# IO_Combo_LED_Monitor.net
KiCad netlist of a schematic drawn in Altium Designer
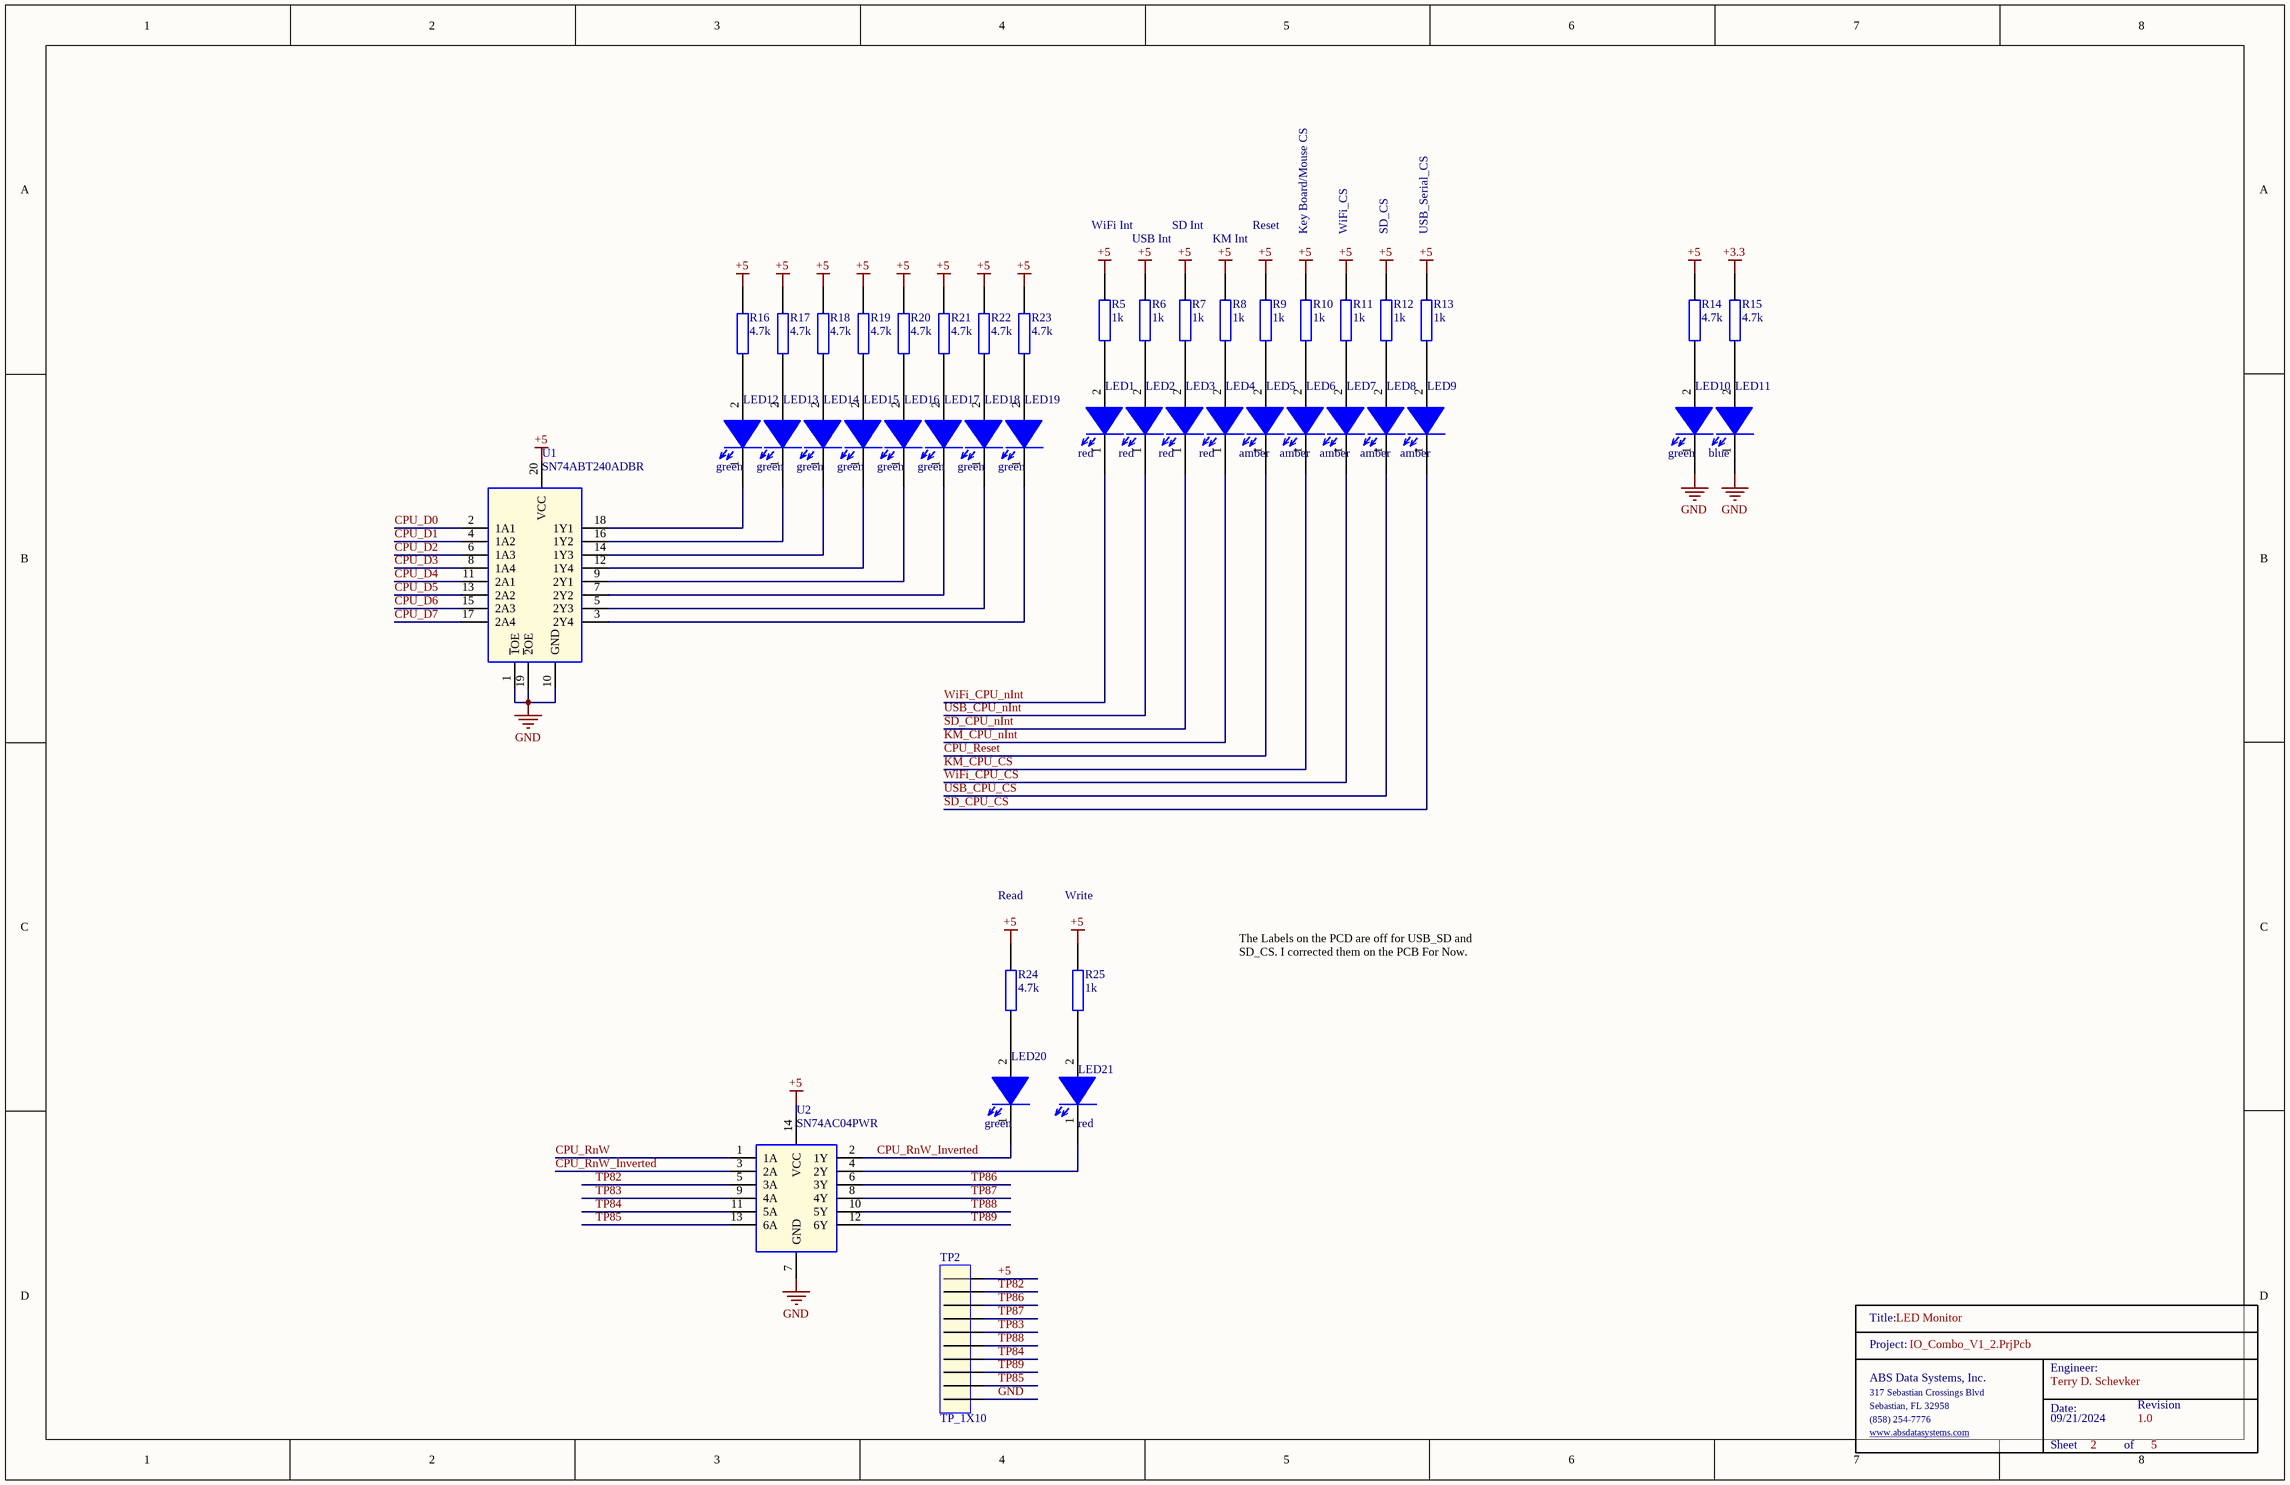
[diagram p0: IO_Combo_LED_Monitor.SchDoc]

(export (version "E")
  (design (tool "Eeschema 10.0.6"))
  (components
    (comp (ref "LED1")
      (value "red")
      (footprint "0603_Diode")
      (description "Wurth Elektronik 0603 red")
      (fields
        (field (name "MANUFACTURER") "Wurth Electronics")
        (field (name "MANUFACTURER PART NUMBER") "150060GS75000")
      )
      (libsource (lib "Misc") (part "150060RS75000"))
    )
    (comp (ref "LED2")
      (value "red")
      (footprint "0603_Diode")
      (description "Wurth Elektronik 0603 red")
      (fields
        (field (name "MANUFACTURER") "Wurth Electronics")
        (field (name "MANUFACTURER PART NUMBER") "150060GS75000")
      )
      (libsource (lib "Misc") (part "150060RS75000"))
    )
    (comp (ref "LED3")
      (value "red")
      (footprint "0603_Diode")
      (description "Wurth Elektronik 0603 red")
      (fields
        (field (name "MANUFACTURER") "Wurth Electronics")
        (field (name "MANUFACTURER PART NUMBER") "150060GS75000")
      )
      (libsource (lib "Misc") (part "150060RS75000"))
    )
    (comp (ref "LED4")
      (value "red")
      (footprint "0603_Diode")
      (description "Wurth Elektronik 0603 red")
      (fields
        (field (name "MANUFACTURER") "Wurth Electronics")
        (field (name "MANUFACTURER PART NUMBER") "150060GS75000")
      )
      (libsource (lib "Misc") (part "150060RS75000"))
    )
    (comp (ref "LED5")
      (value "amber")
      (footprint "0603_Diode")
      (description "Wurth Elektronik 0603 amber")
      (fields
        (field (name "MANUFACTURER") "Wurth Electronics")
        (field (name "MANUFACTURER PART NUMBER") "150060GS75000")
      )
      (libsource (lib "Misc") (part "150060AS75000"))
    )
    (comp (ref "LED6")
      (value "amber")
      (footprint "0603_Diode")
      (description "Wurth Elektronik 0603 amber")
      (fields
        (field (name "MANUFACTURER") "Wurth Electronics")
        (field (name "MANUFACTURER PART NUMBER") "150060GS75000")
      )
      (libsource (lib "Misc") (part "150060AS75000"))
    )
    (comp (ref "LED7")
      (value "amber")
      (footprint "0603_Diode")
      (description "Wurth Elektronik 0603 amber")
      (fields
        (field (name "MANUFACTURER") "Wurth Electronics")
        (field (name "MANUFACTURER PART NUMBER") "150060GS75000")
      )
      (libsource (lib "Misc") (part "150060AS75000"))
    )
    (comp (ref "LED8")
      (value "amber")
      (footprint "0603_Diode")
      (description "Wurth Elektronik 0603 amber")
      (fields
        (field (name "MANUFACTURER") "Wurth Electronics")
        (field (name "MANUFACTURER PART NUMBER") "150060GS75000")
      )
      (libsource (lib "Misc") (part "150060AS75000"))
    )
    (comp (ref "LED9")
      (value "amber")
      (footprint "0603_Diode")
      (description "Wurth Elektronik 0603 amber")
      (fields
        (field (name "MANUFACTURER") "Wurth Electronics")
        (field (name "MANUFACTURER PART NUMBER") "150060GS75000")
      )
      (libsource (lib "Misc") (part "150060AS75000"))
    )
    (comp (ref "LED10")
      (value "green")
      (footprint "0603_Diode")
      (description "Wurth Elektronik 0603 green")
      (fields
        (field (name "MANUFACTURER") "Wurth Electronics")
        (field (name "MANUFACTURER PART NUMBER") "150060GS75000")
      )
      (libsource (lib "Misc") (part "150060GS75000"))
    )
    (comp (ref "LED11")
      (value "blue")
      (footprint "0603_Diode")
      (description "Wurth Elektronik 0603 blue")
      (fields
        (field (name "MANUFACTURER") "Wurth Electronics")
        (field (name "MANUFACTURER PART NUMBER") "150060GS75000")
      )
      (libsource (lib "Misc") (part "150060BS75000"))
    )
    (comp (ref "LED12")
      (value "green")
      (footprint "0603_Diode")
      (description "Wurth Elektronik 0603 green")
      (fields
        (field (name "MANUFACTURER") "Wurth Electronics")
        (field (name "MANUFACTURER PART NUMBER") "150060GS75000")
      )
      (libsource (lib "Misc") (part "150060GS75000"))
    )
    (comp (ref "LED13")
      (value "green")
      (footprint "0603_Diode")
      (description "Wurth Elektronik 0603 green")
      (fields
        (field (name "MANUFACTURER") "Wurth Electronics")
        (field (name "MANUFACTURER PART NUMBER") "150060GS75000")
      )
      (libsource (lib "Misc") (part "150060GS75000"))
    )
    (comp (ref "LED14")
      (value "green")
      (footprint "0603_Diode")
      (description "Wurth Elektronik 0603 green")
      (fields
        (field (name "MANUFACTURER") "Wurth Electronics")
        (field (name "MANUFACTURER PART NUMBER") "150060GS75000")
      )
      (libsource (lib "Misc") (part "150060GS75000"))
    )
    (comp (ref "LED15")
      (value "green")
      (footprint "0603_Diode")
      (description "Wurth Elektronik 0603 green")
      (fields
        (field (name "MANUFACTURER") "Wurth Electronics")
        (field (name "MANUFACTURER PART NUMBER") "150060GS75000")
      )
      (libsource (lib "Misc") (part "150060GS75000"))
    )
    (comp (ref "LED16")
      (value "green")
      (footprint "0603_Diode")
      (description "Wurth Elektronik 0603 green")
      (fields
        (field (name "MANUFACTURER") "Wurth Electronics")
        (field (name "MANUFACTURER PART NUMBER") "150060GS75000")
      )
      (libsource (lib "Misc") (part "150060GS75000"))
    )
    (comp (ref "LED17")
      (value "green")
      (footprint "0603_Diode")
      (description "Wurth Elektronik 0603 green")
      (fields
        (field (name "MANUFACTURER") "Wurth Electronics")
        (field (name "MANUFACTURER PART NUMBER") "150060GS75000")
      )
      (libsource (lib "Misc") (part "150060GS75000"))
    )
    (comp (ref "LED18")
      (value "green")
      (footprint "0603_Diode")
      (description "Wurth Elektronik 0603 green")
      (fields
        (field (name "MANUFACTURER") "Wurth Electronics")
        (field (name "MANUFACTURER PART NUMBER") "150060GS75000")
      )
      (libsource (lib "Misc") (part "150060GS75000"))
    )
    (comp (ref "LED19")
      (value "green")
      (footprint "0603_Diode")
      (description "Wurth Elektronik 0603 green")
      (fields
        (field (name "MANUFACTURER") "Wurth Electronics")
        (field (name "MANUFACTURER PART NUMBER") "150060GS75000")
      )
      (libsource (lib "Misc") (part "150060GS75000"))
    )
    (comp (ref "LED20")
      (value "green")
      (footprint "0603_Diode")
      (description "Wurth Elektronik 0603 green")
      (fields
        (field (name "MANUFACTURER") "Wurth Electronics")
        (field (name "MANUFACTURER PART NUMBER") "150060GS75000")
      )
      (libsource (lib "Misc") (part "150060GS75000"))
    )
    (comp (ref "LED21")
      (value "red")
      (footprint "0603_Diode")
      (description "Wurth Elektronik 0603 red")
      (fields
        (field (name "MANUFACTURER") "Wurth Electronics")
        (field (name "MANUFACTURER PART NUMBER") "150060GS75000")
      )
      (libsource (lib "Misc") (part "150060RS75000"))
    )
    (comp (ref "R5")
      (value "1k")
      (footprint "0603")
      (description "YAGEO 0603 1k ohm")
      (fields
        (field (name "MOUSER PART NUMBER") "603-RC0603JR-070RL")
        (field (name "MANUFACTURER_PART_NUMBER") "RC0603JR-070RL")
      )
      (libsource (lib "Resistors") (part "AC0603FR-7W1KL_1"))
    )
    (comp (ref "R6")
      (value "1k")
      (footprint "0603")
      (description "YAGEO 0603 1k ohm")
      (fields
        (field (name "MOUSER PART NUMBER") "603-RC0603JR-070RL")
        (field (name "MANUFACTURER_PART_NUMBER") "RC0603JR-070RL")
      )
      (libsource (lib "Resistors") (part "AC0603FR-7W1KL_1"))
    )
    (comp (ref "R7")
      (value "1k")
      (footprint "0603")
      (description "YAGEO 0603 1k ohm")
      (fields
        (field (name "MOUSER PART NUMBER") "603-RC0603JR-070RL")
        (field (name "MANUFACTURER_PART_NUMBER") "RC0603JR-070RL")
      )
      (libsource (lib "Resistors") (part "AC0603FR-7W1KL_1"))
    )
    (comp (ref "R8")
      (value "1k")
      (footprint "0603")
      (description "YAGEO 0603 1k ohm")
      (fields
        (field (name "MOUSER PART NUMBER") "603-RC0603JR-070RL")
        (field (name "MANUFACTURER_PART_NUMBER") "RC0603JR-070RL")
      )
      (libsource (lib "Resistors") (part "AC0603FR-7W1KL_1"))
    )
    (comp (ref "R9")
      (value "1k")
      (footprint "0603")
      (description "YAGEO 0603 1k ohm")
      (fields
        (field (name "MOUSER PART NUMBER") "603-RC0603JR-070RL")
        (field (name "MANUFACTURER_PART_NUMBER") "RC0603JR-070RL")
      )
      (libsource (lib "Resistors") (part "AC0603FR-7W1KL_1"))
    )
    (comp (ref "R10")
      (value "1k")
      (footprint "0603")
      (description "YAGEO 0603 1k ohm")
      (fields
        (field (name "MOUSER PART NUMBER") "603-RC0603JR-070RL")
        (field (name "MANUFACTURER_PART_NUMBER") "RC0603JR-070RL")
      )
      (libsource (lib "Resistors") (part "AC0603FR-7W1KL_1"))
    )
    (comp (ref "R11")
      (value "1k")
      (footprint "0603")
      (description "YAGEO 0603 1k ohm")
      (fields
        (field (name "MOUSER PART NUMBER") "603-RC0603JR-070RL")
        (field (name "MANUFACTURER_PART_NUMBER") "RC0603JR-070RL")
      )
      (libsource (lib "Resistors") (part "AC0603FR-7W1KL_1"))
    )
    (comp (ref "R12")
      (value "1k")
      (footprint "0603")
      (description "YAGEO 0603 1k ohm")
      (fields
        (field (name "MOUSER PART NUMBER") "603-RC0603JR-070RL")
        (field (name "MANUFACTURER_PART_NUMBER") "RC0603JR-070RL")
      )
      (libsource (lib "Resistors") (part "AC0603FR-7W1KL_1"))
    )
    (comp (ref "R13")
      (value "1k")
      (footprint "0603")
      (description "YAGEO 0603 1k ohm")
      (fields
        (field (name "MOUSER PART NUMBER") "603-RC0603JR-070RL")
        (field (name "MANUFACTURER_PART_NUMBER") "RC0603JR-070RL")
      )
      (libsource (lib "Resistors") (part "AC0603FR-7W1KL_1"))
    )
    (comp (ref "R14")
      (value "4.7k")
      (footprint "0603")
      (description "YAGEO 0603 4.7k")
      (fields
        (field (name "MOUSER PART NUMBER") "603-RC0603JR-070RL")
        (field (name "MANUFACTURER_PART_NUMBER") "RC0603JR-070RL")
      )
      (libsource (lib "Resistors") (part "RC0603FR-104K7L"))
    )
    (comp (ref "R15")
      (value "4.7k")
      (footprint "0603")
      (description "YAGEO 0603 4.7k")
      (fields
        (field (name "MOUSER PART NUMBER") "603-RC0603JR-070RL")
        (field (name "MANUFACTURER_PART_NUMBER") "RC0603JR-070RL")
      )
      (libsource (lib "Resistors") (part "RC0603FR-104K7L"))
    )
    (comp (ref "R16")
      (value "4.7k")
      (footprint "0603")
      (description "YAGEO 0603 4.7k")
      (fields
        (field (name "MOUSER PART NUMBER") "603-RC0603JR-070RL")
        (field (name "MANUFACTURER_PART_NUMBER") "RC0603JR-070RL")
      )
      (libsource (lib "Resistors") (part "RC0603FR-104K7L"))
    )
    (comp (ref "R17")
      (value "4.7k")
      (footprint "0603")
      (description "YAGEO 0603 4.7k")
      (fields
        (field (name "MOUSER PART NUMBER") "603-RC0603JR-070RL")
        (field (name "MANUFACTURER_PART_NUMBER") "RC0603JR-070RL")
      )
      (libsource (lib "Resistors") (part "RC0603FR-104K7L"))
    )
    (comp (ref "R18")
      (value "4.7k")
      (footprint "0603")
      (description "YAGEO 0603 4.7k")
      (fields
        (field (name "MOUSER PART NUMBER") "603-RC0603JR-070RL")
        (field (name "MANUFACTURER_PART_NUMBER") "RC0603JR-070RL")
      )
      (libsource (lib "Resistors") (part "RC0603FR-104K7L"))
    )
    (comp (ref "R19")
      (value "4.7k")
      (footprint "0603")
      (description "YAGEO 0603 4.7k")
      (fields
        (field (name "MOUSER PART NUMBER") "603-RC0603JR-070RL")
        (field (name "MANUFACTURER_PART_NUMBER") "RC0603JR-070RL")
      )
      (libsource (lib "Resistors") (part "RC0603FR-104K7L"))
    )
    (comp (ref "R20")
      (value "4.7k")
      (footprint "0603")
      (description "YAGEO 0603 4.7k")
      (fields
        (field (name "MOUSER PART NUMBER") "603-RC0603JR-070RL")
        (field (name "MANUFACTURER_PART_NUMBER") "RC0603JR-070RL")
      )
      (libsource (lib "Resistors") (part "RC0603FR-104K7L"))
    )
    (comp (ref "R21")
      (value "4.7k")
      (footprint "0603")
      (description "YAGEO 0603 4.7k")
      (fields
        (field (name "MOUSER PART NUMBER") "603-RC0603JR-070RL")
        (field (name "MANUFACTURER_PART_NUMBER") "RC0603JR-070RL")
      )
      (libsource (lib "Resistors") (part "RC0603FR-104K7L"))
    )
    (comp (ref "R22")
      (value "4.7k")
      (footprint "0603")
      (description "YAGEO 0603 4.7k")
      (fields
        (field (name "MOUSER PART NUMBER") "603-RC0603JR-070RL")
        (field (name "MANUFACTURER_PART_NUMBER") "RC0603JR-070RL")
      )
      (libsource (lib "Resistors") (part "RC0603FR-104K7L"))
    )
    (comp (ref "R23")
      (value "4.7k")
      (footprint "0603")
      (description "YAGEO 0603 4.7k")
      (fields
        (field (name "MOUSER PART NUMBER") "603-RC0603JR-070RL")
        (field (name "MANUFACTURER_PART_NUMBER") "RC0603JR-070RL")
      )
      (libsource (lib "Resistors") (part "RC0603FR-104K7L"))
    )
    (comp (ref "R24")
      (value "4.7k")
      (footprint "0603")
      (description "YAGEO 0603 4.7k")
      (fields
        (field (name "MOUSER PART NUMBER") "603-RC0603JR-070RL")
        (field (name "MANUFACTURER_PART_NUMBER") "RC0603JR-070RL")
      )
      (libsource (lib "Resistors") (part "RC0603FR-104K7L"))
    )
    (comp (ref "R25")
      (value "1k")
      (footprint "0603")
      (description "YAGEO 0603 1k ohm")
      (fields
        (field (name "MOUSER PART NUMBER") "603-RC0603JR-070RL")
        (field (name "MANUFACTURER_PART_NUMBER") "RC0603JR-070RL")
      )
      (libsource (lib "Resistors") (part "AC0603FR-7W1KL_1"))
    )
    (comp (ref "TP2")
      (value "TP_1X10")
      (footprint "TP_1X10")
      (fields
        (field (name "MANUFACTURER") "Samtec")
        (field (name "MANUFACTURER PART NUMBER") "TST-105-01-G-D")
      )
      (libsource (lib "Misc") (part "TP_1X10"))
    )
    (comp (ref "U1")
      (value "SN74ABT240ADBR")
      (footprint "SOP65P780X200-20N")
      (description "Octal Buffers/Drivers With 3-State Outputs")
      (fields (field (name "MOUSER PART NUMBER") "595-SN74ABT240ADBR"))
      (libsource (lib "Logic") (part "SN74ABT240ADBR"))
    )
    (comp (ref "U2")
      (value "SN74AC04PWR")
      (footprint "SOP65P640X120-14N")
      (description "Hex Inverters")
      (fields (field (name "MOUSER PART NUMBER") "595-SN74AC04PWR"))
      (libsource (lib "Logic") (part "SN74AC04PWR"))
    )
  )
  (nets
    (net (code "1") (name "+3.3") (class "Default")
      (node (ref "R15") (pin "2") (pinfunction "2_2") (pintype "passive"))
    )
    (net (code "2") (name "+5") (class "Default")
      (node (ref "R10") (pin "2") (pinfunction "2_2") (pintype "passive"))
      (node (ref "R11") (pin "2") (pinfunction "2_2") (pintype "passive"))
      (node (ref "R12") (pin "2") (pinfunction "2_2") (pintype "passive"))
      (node (ref "R13") (pin "2") (pinfunction "2_2") (pintype "passive"))
      (node (ref "R14") (pin "2") (pinfunction "2_2") (pintype "passive"))
      (node (ref "R16") (pin "2") (pinfunction "2_2") (pintype "passive"))
      (node (ref "R17") (pin "2") (pinfunction "2_2") (pintype "passive"))
      (node (ref "R18") (pin "2") (pinfunction "2_2") (pintype "passive"))
      (node (ref "R19") (pin "2") (pinfunction "2_2") (pintype "passive"))
      (node (ref "R20") (pin "2") (pinfunction "2_2") (pintype "passive"))
      (node (ref "R21") (pin "2") (pinfunction "2_2") (pintype "passive"))
      (node (ref "R22") (pin "2") (pinfunction "2_2") (pintype "passive"))
      (node (ref "R23") (pin "2") (pinfunction "2_2") (pintype "passive"))
      (node (ref "R24") (pin "2") (pinfunction "2_2") (pintype "passive"))
      (node (ref "R25") (pin "2") (pinfunction "2_2") (pintype "passive"))
      (node (ref "R5") (pin "2") (pinfunction "2_2") (pintype "passive"))
      (node (ref "R6") (pin "2") (pinfunction "2_2") (pintype "passive"))
      (node (ref "R7") (pin "2") (pinfunction "2_2") (pintype "passive"))
      (node (ref "R8") (pin "2") (pinfunction "2_2") (pintype "passive"))
      (node (ref "R9") (pin "2") (pinfunction "2_2") (pintype "passive"))
      (node (ref "TP2") (pin "1") (pinfunction "1_1") (pintype "passive"))
      (node (ref "U1") (pin "20") (pinfunction "VCC_20") (pintype "passive"))
      (node (ref "U2") (pin "14") (pinfunction "VCC_14") (pintype "passive"))
    )
    (net (code "3") (name "/CPU_D0") (class "Default")
      (node (ref "U1") (pin "2") (pinfunction "1A1_2") (pintype "passive"))
    )
    (net (code "4") (name "/CPU_D1") (class "Default")
      (node (ref "U1") (pin "4") (pinfunction "1A2_4") (pintype "passive"))
    )
    (net (code "5") (name "/CPU_D2") (class "Default")
      (node (ref "U1") (pin "6") (pinfunction "1A3_6") (pintype "passive"))
    )
    (net (code "6") (name "/CPU_D3") (class "Default")
      (node (ref "U1") (pin "8") (pinfunction "1A4_8") (pintype "passive"))
    )
    (net (code "7") (name "/CPU_D4") (class "Default")
      (node (ref "U1") (pin "11") (pinfunction "2A1_11") (pintype "passive"))
    )
    (net (code "8") (name "/CPU_D5") (class "Default")
      (node (ref "U1") (pin "13") (pinfunction "2A2_13") (pintype "passive"))
    )
    (net (code "9") (name "/CPU_D6") (class "Default")
      (node (ref "U1") (pin "15") (pinfunction "2A3_15") (pintype "passive"))
    )
    (net (code "10") (name "/CPU_D7") (class "Default")
      (node (ref "U1") (pin "17") (pinfunction "2A4_17") (pintype "passive"))
    )
    (net (code "11") (name "/CPU_Reset") (class "Default")
      (node (ref "LED5") (pin "1") (pinfunction "K_1") (pintype "passive"))
    )
    (net (code "12") (name "/CPU_RnW") (class "Default")
      (node (ref "U2") (pin "1") (pinfunction "1A_1") (pintype "passive"))
    )
    (net (code "13") (name "/CPU_RnW_Inverted") (class "Default")
      (node (ref "LED20") (pin "1") (pinfunction "K_1") (pintype "passive"))
      (node (ref "U2") (pin "2") (pinfunction "1Y_2") (pintype "passive"))
      (node (ref "U2") (pin "3") (pinfunction "2A_3") (pintype "passive"))
    )
    (net (code "14") (name "/KM_CPU_CS") (class "Default")
      (node (ref "LED6") (pin "1") (pinfunction "K_1") (pintype "passive"))
    )
    (net (code "15") (name "/KM_CPU_nInt") (class "Default")
      (node (ref "LED4") (pin "1") (pinfunction "K_1") (pintype "passive"))
    )
    (net (code "16") (name "/SD_CPU_CS") (class "Default")
      (node (ref "LED9") (pin "1") (pinfunction "K_1") (pintype "passive"))
    )
    (net (code "17") (name "/SD_CPU_nInt") (class "Default")
      (node (ref "LED3") (pin "1") (pinfunction "K_1") (pintype "passive"))
    )
    (net (code "18") (name "/TP82") (class "Default")
      (node (ref "TP2") (pin "2") (pinfunction "2_2") (pintype "passive"))
      (node (ref "U2") (pin "5") (pinfunction "3A_5") (pintype "passive"))
    )
    (net (code "19") (name "/TP83") (class "Default")
      (node (ref "TP2") (pin "5") (pinfunction "5_5") (pintype "passive"))
      (node (ref "U2") (pin "9") (pinfunction "4A_9") (pintype "passive"))
    )
    (net (code "20") (name "/TP84") (class "Default")
      (node (ref "TP2") (pin "7") (pinfunction "7_7") (pintype "passive"))
      (node (ref "U2") (pin "11") (pinfunction "5A_11") (pintype "passive"))
    )
    (net (code "21") (name "/TP85") (class "Default")
      (node (ref "TP2") (pin "9") (pinfunction "9_9") (pintype "passive"))
      (node (ref "U2") (pin "13") (pinfunction "6A_13") (pintype "passive"))
    )
    (net (code "22") (name "/TP86") (class "Default")
      (node (ref "TP2") (pin "3") (pinfunction "3_3") (pintype "passive"))
      (node (ref "U2") (pin "6") (pinfunction "3Y_6") (pintype "passive"))
    )
    (net (code "23") (name "/TP87") (class "Default")
      (node (ref "TP2") (pin "4") (pinfunction "4_4") (pintype "passive"))
      (node (ref "U2") (pin "8") (pinfunction "4Y_8") (pintype "passive"))
    )
    (net (code "24") (name "/TP88") (class "Default")
      (node (ref "TP2") (pin "6") (pinfunction "6_6") (pintype "passive"))
      (node (ref "U2") (pin "10") (pinfunction "5Y_10") (pintype "passive"))
    )
    (net (code "25") (name "/TP89") (class "Default")
      (node (ref "TP2") (pin "8") (pinfunction "8_8") (pintype "passive"))
      (node (ref "U2") (pin "12") (pinfunction "6Y_12") (pintype "passive"))
    )
    (net (code "26") (name "/USB_CPU_CS") (class "Default")
      (node (ref "LED8") (pin "1") (pinfunction "K_1") (pintype "passive"))
    )
    (net (code "27") (name "/USB_CPU_nInt") (class "Default")
      (node (ref "LED2") (pin "1") (pinfunction "K_1") (pintype "passive"))
    )
    (net (code "28") (name "/WiFi_CPU_CS") (class "Default")
      (node (ref "LED7") (pin "1") (pinfunction "K_1") (pintype "passive"))
    )
    (net (code "29") (name "/WiFi_CPU_nInt") (class "Default")
      (node (ref "LED1") (pin "1") (pinfunction "K_1") (pintype "passive"))
    )
    (net (code "30") (name "GND") (class "Default")
      (node (ref "LED10") (pin "1") (pinfunction "K_1") (pintype "passive"))
      (node (ref "LED11") (pin "1") (pinfunction "K_1") (pintype "passive"))
      (node (ref "TP2") (pin "10") (pinfunction "10_10") (pintype "passive"))
      (node (ref "U1") (pin "1") (pinfunction "~{1}OE_1") (pintype "passive"))
      (node (ref "U1") (pin "10") (pinfunction "GND_10") (pintype "passive"))
      (node (ref "U1") (pin "19") (pinfunction "~{2}OE_19") (pintype "passive"))
      (node (ref "U2") (pin "7") (pinfunction "GND_7") (pintype "passive"))
    )
    (net (code "31") (name "Net-(LED1-A)") (class "Default")
      (node (ref "LED1") (pin "2") (pinfunction "A_2") (pintype "passive"))
      (node (ref "R5") (pin "1") (pinfunction "1_1") (pintype "passive"))
    )
    (net (code "32") (name "Net-(LED2-A)") (class "Default")
      (node (ref "LED2") (pin "2") (pinfunction "A_2") (pintype "passive"))
      (node (ref "R6") (pin "1") (pinfunction "1_1") (pintype "passive"))
    )
    (net (code "33") (name "Net-(LED3-A)") (class "Default")
      (node (ref "LED3") (pin "2") (pinfunction "A_2") (pintype "passive"))
      (node (ref "R7") (pin "1") (pinfunction "1_1") (pintype "passive"))
    )
    (net (code "34") (name "Net-(LED4-A)") (class "Default")
      (node (ref "LED4") (pin "2") (pinfunction "A_2") (pintype "passive"))
      (node (ref "R8") (pin "1") (pinfunction "1_1") (pintype "passive"))
    )
    (net (code "35") (name "Net-(LED5-A)") (class "Default")
      (node (ref "LED5") (pin "2") (pinfunction "A_2") (pintype "passive"))
      (node (ref "R9") (pin "1") (pinfunction "1_1") (pintype "passive"))
    )
    (net (code "36") (name "Net-(LED6-A)") (class "Default")
      (node (ref "LED6") (pin "2") (pinfunction "A_2") (pintype "passive"))
      (node (ref "R10") (pin "1") (pinfunction "1_1") (pintype "passive"))
    )
    (net (code "37") (name "Net-(LED7-A)") (class "Default")
      (node (ref "LED7") (pin "2") (pinfunction "A_2") (pintype "passive"))
      (node (ref "R11") (pin "1") (pinfunction "1_1") (pintype "passive"))
    )
    (net (code "38") (name "Net-(LED8-A)") (class "Default")
      (node (ref "LED8") (pin "2") (pinfunction "A_2") (pintype "passive"))
      (node (ref "R12") (pin "1") (pinfunction "1_1") (pintype "passive"))
    )
    (net (code "39") (name "Net-(LED9-A)") (class "Default")
      (node (ref "LED9") (pin "2") (pinfunction "A_2") (pintype "passive"))
      (node (ref "R13") (pin "1") (pinfunction "1_1") (pintype "passive"))
    )
    (net (code "40") (name "Net-(LED10-A)") (class "Default")
      (node (ref "LED10") (pin "2") (pinfunction "A_2") (pintype "passive"))
      (node (ref "R14") (pin "1") (pinfunction "1_1") (pintype "passive"))
    )
    (net (code "41") (name "Net-(LED11-A)") (class "Default")
      (node (ref "LED11") (pin "2") (pinfunction "A_2") (pintype "passive"))
      (node (ref "R15") (pin "1") (pinfunction "1_1") (pintype "passive"))
    )
    (net (code "42") (name "Net-(LED12-A)") (class "Default")
      (node (ref "LED12") (pin "2") (pinfunction "A_2") (pintype "passive"))
      (node (ref "R16") (pin "1") (pinfunction "1_1") (pintype "passive"))
    )
    (net (code "43") (name "Net-(LED12-K)") (class "Default")
      (node (ref "LED12") (pin "1") (pinfunction "K_1") (pintype "passive"))
      (node (ref "U1") (pin "18") (pinfunction "1Y1_18") (pintype "passive"))
    )
    (net (code "44") (name "Net-(LED13-A)") (class "Default")
      (node (ref "LED13") (pin "2") (pinfunction "A_2") (pintype "passive"))
      (node (ref "R17") (pin "1") (pinfunction "1_1") (pintype "passive"))
    )
    (net (code "45") (name "Net-(LED13-K)") (class "Default")
      (node (ref "LED13") (pin "1") (pinfunction "K_1") (pintype "passive"))
      (node (ref "U1") (pin "16") (pinfunction "1Y2_16") (pintype "passive"))
    )
    (net (code "46") (name "Net-(LED14-A)") (class "Default")
      (node (ref "LED14") (pin "2") (pinfunction "A_2") (pintype "passive"))
      (node (ref "R18") (pin "1") (pinfunction "1_1") (pintype "passive"))
    )
    (net (code "47") (name "Net-(LED14-K)") (class "Default")
      (node (ref "LED14") (pin "1") (pinfunction "K_1") (pintype "passive"))
      (node (ref "U1") (pin "14") (pinfunction "1Y3_14") (pintype "passive"))
    )
    (net (code "48") (name "Net-(LED15-A)") (class "Default")
      (node (ref "LED15") (pin "2") (pinfunction "A_2") (pintype "passive"))
      (node (ref "R19") (pin "1") (pinfunction "1_1") (pintype "passive"))
    )
    (net (code "49") (name "Net-(LED15-K)") (class "Default")
      (node (ref "LED15") (pin "1") (pinfunction "K_1") (pintype "passive"))
      (node (ref "U1") (pin "12") (pinfunction "1Y4_12") (pintype "passive"))
    )
    (net (code "50") (name "Net-(LED16-A)") (class "Default")
      (node (ref "LED16") (pin "2") (pinfunction "A_2") (pintype "passive"))
      (node (ref "R20") (pin "1") (pinfunction "1_1") (pintype "passive"))
    )
    (net (code "51") (name "Net-(LED16-K)") (class "Default")
      (node (ref "LED16") (pin "1") (pinfunction "K_1") (pintype "passive"))
      (node (ref "U1") (pin "9") (pinfunction "2Y1_9") (pintype "passive"))
    )
    (net (code "52") (name "Net-(LED17-A)") (class "Default")
      (node (ref "LED17") (pin "2") (pinfunction "A_2") (pintype "passive"))
      (node (ref "R21") (pin "1") (pinfunction "1_1") (pintype "passive"))
    )
    (net (code "53") (name "Net-(LED17-K)") (class "Default")
      (node (ref "LED17") (pin "1") (pinfunction "K_1") (pintype "passive"))
      (node (ref "U1") (pin "7") (pinfunction "2Y2_7") (pintype "passive"))
    )
    (net (code "54") (name "Net-(LED18-A)") (class "Default")
      (node (ref "LED18") (pin "2") (pinfunction "A_2") (pintype "passive"))
      (node (ref "R22") (pin "1") (pinfunction "1_1") (pintype "passive"))
    )
    (net (code "55") (name "Net-(LED18-K)") (class "Default")
      (node (ref "LED18") (pin "1") (pinfunction "K_1") (pintype "passive"))
      (node (ref "U1") (pin "5") (pinfunction "2Y3_5") (pintype "passive"))
    )
    (net (code "56") (name "Net-(LED19-A)") (class "Default")
      (node (ref "LED19") (pin "2") (pinfunction "A_2") (pintype "passive"))
      (node (ref "R23") (pin "1") (pinfunction "1_1") (pintype "passive"))
    )
    (net (code "57") (name "Net-(LED19-K)") (class "Default")
      (node (ref "LED19") (pin "1") (pinfunction "K_1") (pintype "passive"))
      (node (ref "U1") (pin "3") (pinfunction "2Y4_3") (pintype "passive"))
    )
    (net (code "58") (name "Net-(LED20-A)") (class "Default")
      (node (ref "LED20") (pin "2") (pinfunction "A_2") (pintype "passive"))
      (node (ref "R24") (pin "1") (pinfunction "1_1") (pintype "passive"))
    )
    (net (code "59") (name "Net-(LED21-A)") (class "Default")
      (node (ref "LED21") (pin "2") (pinfunction "A_2") (pintype "passive"))
      (node (ref "R25") (pin "1") (pinfunction "1_1") (pintype "passive"))
    )
    (net (code "60") (name "Net-(LED21-K)") (class "Default")
      (node (ref "LED21") (pin "1") (pinfunction "K_1") (pintype "passive"))
      (node (ref "U2") (pin "4") (pinfunction "2Y_4") (pintype "passive"))
    )
  )
)
